# Robotic_armmodified_3pin.net
KiCad netlist of a schematic drawn in Altium Designer
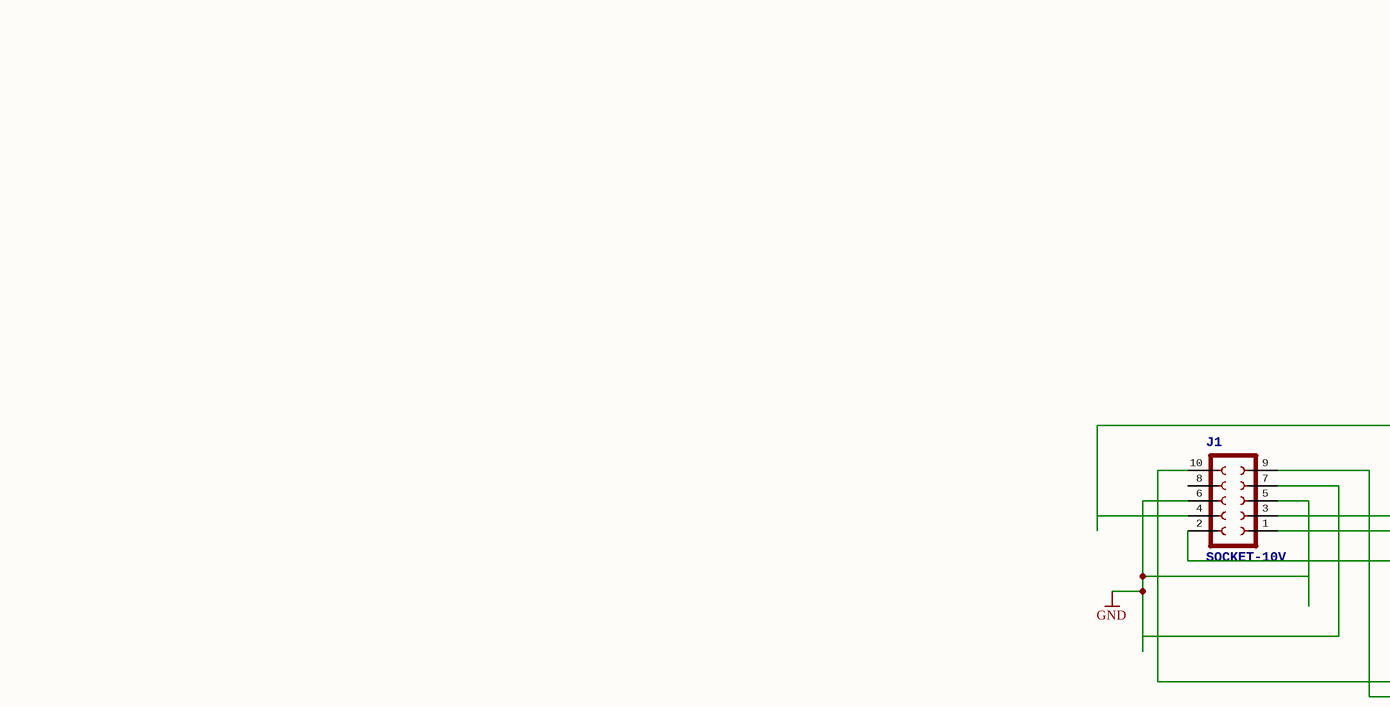
[diagram p0: Robotic armmodified 3pin.SchDoc, left]
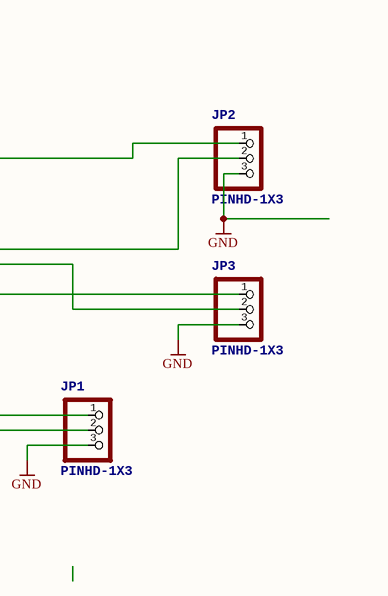
[diagram p1: Robotic armmodified 3pin.SchDoc, middle]

(export (version "E")
  (design (tool "Eeschema 10.0.6"))
  (components
    (comp (ref "J1")
      (value "SOCKET-10V")
      (footprint "S10V")
      (description "10 pin PCB Socket (3m 85xx/51xx)")
      (libsource (lib "con-3m-skt-header") (part "SOCKET-10V"))
    )
    (comp (ref "JP1")
      (value "PINHD-1X3")
      (footprint "1X03")
      (description "PIN HEADER")
      (libsource (lib "pinhead") (part "PINHD-1X3"))
    )
    (comp (ref "JP2")
      (value "PINHD-1X3")
      (footprint "1X03")
      (description "PIN HEADER")
      (libsource (lib "pinhead") (part "PINHD-1X3"))
    )
    (comp (ref "JP3")
      (value "PINHD-1X3")
      (footprint "1X03")
      (description "PIN HEADER")
      (libsource (lib "pinhead") (part "PINHD-1X3"))
    )
    (comp (ref "MRM1")
      (value "MRM")
      (footprint "LOL")
      (fields (field (name "MRMLOGO") "MRM Logo"))
      (libsource (lib "MRM") (part "MRM"))
    )
  )
  (nets
    (net (code "1") (name "GND") (class "Default")
      (node (ref "J1") (pin "5") (pinfunction "5_5") (pintype "passive"))
      (node (ref "J1") (pin "6") (pinfunction "6_6") (pintype "passive"))
      (node (ref "J1") (pin "7") (pinfunction "7_7") (pintype "passive"))
      (node (ref "JP1") (pin "3") (pinfunction "3_3") (pintype "passive"))
      (node (ref "JP2") (pin "3") (pinfunction "3_3") (pintype "passive"))
      (node (ref "JP3") (pin "3") (pinfunction "3_3") (pintype "passive"))
    )
    (net (code "2") (name "Net-(J1-Pad1)") (class "Default")
      (node (ref "J1") (pin "1") (pinfunction "1_1") (pintype "passive"))
      (node (ref "JP3") (pin "2") (pinfunction "2_2") (pintype "passive"))
    )
    (net (code "3") (name "Net-(J1-Pad2)") (class "Default")
      (node (ref "J1") (pin "2") (pinfunction "2_2") (pintype "passive"))
      (node (ref "JP3") (pin "1") (pinfunction "1_1") (pintype "passive"))
    )
    (net (code "4") (name "Net-(J1-Pad3)") (class "Default")
      (node (ref "J1") (pin "3") (pinfunction "3_3") (pintype "passive"))
      (node (ref "JP2") (pin "2") (pinfunction "2_2") (pintype "passive"))
    )
    (net (code "5") (name "Net-(J1-Pad4)") (class "Default")
      (node (ref "J1") (pin "4") (pinfunction "4_4") (pintype "passive"))
      (node (ref "JP2") (pin "1") (pinfunction "1_1") (pintype "passive"))
    )
    (net (code "6") (name "Net-(J1-Pad9)") (class "Default")
      (node (ref "J1") (pin "9") (pinfunction "9_9") (pintype "passive"))
      (node (ref "JP1") (pin "2") (pinfunction "2_2") (pintype "passive"))
    )
    (net (code "7") (name "Net-(J1-Pad10)") (class "Default")
      (node (ref "J1") (pin "10") (pinfunction "10_10") (pintype "passive"))
      (node (ref "JP1") (pin "1") (pinfunction "1_1") (pintype "passive"))
    )
    (net (code "8") (name "unconnected-(J1-Pad8)") (class "Default")
      (node (ref "J1") (pin "8") (pinfunction "8_8") (pintype "passive"))
    )
  )
)
